# Pressure_sensor_-_SCP1000-D01.net
KiCad netlist of a schematic drawn in Altium Designer
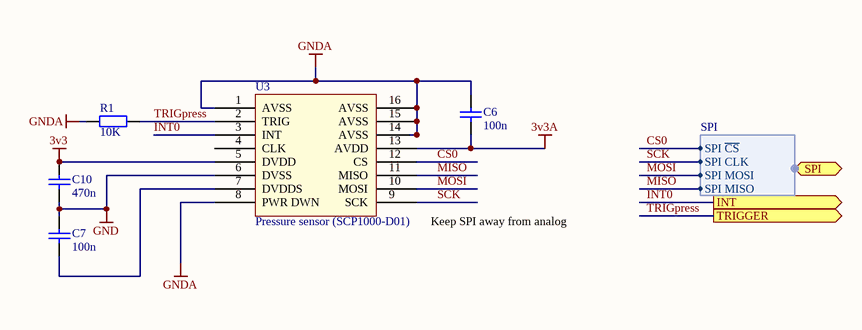
[diagram p0: Pressure sensor - SCP1000-D01.SchDoc]

(export (version "E")
  (design (tool "Eeschema 10.0.6"))
  (components
    (comp (ref "C6")
      (value "100n")
      (footprint "C0805")
      (fields (field (name "TOLERANCE") "0.1") (field (name "AUTHOR") "Willy Pietersz"))
      (libsource (lib "OurDb") (part "cap_NonPolar"))
    )
    (comp (ref "C7")
      (value "100n")
      (footprint "C0805")
      (fields (field (name "TOLERANCE") "0.1") (field (name "AUTHOR") "Willy Pietersz"))
      (libsource (lib "OurDb") (part "cap_NonPolar"))
    )
    (comp (ref "C10")
      (value "470n")
      (footprint "C0805")
      (fields (field (name "TOLERANCE") "0.1") (field (name "AUTHOR") "Willy Pietersz"))
      (libsource (lib "OurDb") (part "cap_NonPolar"))
    )
    (comp (ref "R1")
      (value "10K")
      (footprint "R0805")
      (description "Resistor")
      (fields
        (field (name "POWER") "0.25W")
        (field (name "TOLERANCE") "0.05")
        (field (name "PUBLISHER") "Altium Limited")
        (field (name "AUTHOR") "Willy Pietersz")
      )
      (libsource (lib "OurDb") (part "RESISTOR"))
    )
    (comp (ref "U3")
      (value "Pressure sensor (SCP1000-D01)")
      (footprint "SCP1000-D01")
      (fields (field (name "PART NUMBER") "SCP1000-D01"))
      (libsource (lib "OurDb") (part "SCP1000-D01"))
    )
  )
  (nets
    (net (code "2") (name "/CS0") (class "Default")
      (node (ref "U3") (pin "12") (pinfunction "CS_12") (pintype "passive"))
    )
    (net (code "3") (name "/INT0") (class "Default")
      (node (ref "U3") (pin "3") (pinfunction "INT_3") (pintype "passive"))
    )
    (net (code "4") (name "/MISO") (class "Default")
      (node (ref "U3") (pin "11") (pinfunction "MISO_11") (pintype "passive"))
    )
    (net (code "5") (name "/MOSI") (class "Default")
      (node (ref "U3") (pin "10") (pinfunction "MOSI_10") (pintype "passive"))
    )
    (net (code "6") (name "/SCK") (class "Default")
      (node (ref "U3") (pin "9") (pinfunction "SCK_9") (pintype "passive"))
    )
    (net (code "7") (name "/TRIGpress") (class "Default")
      (node (ref "R1") (pin "2") (pinfunction "2_2") (pintype "passive"))
      (node (ref "U3") (pin "2") (pinfunction "TRIG_2") (pintype "passive"))
    )
    (net (code "9") (name "3v3") (class "Default")
      (node (ref "C10") (pin "2") (pinfunction "2_2") (pintype "passive"))
      (node (ref "U3") (pin "5") (pinfunction "DVDD_5") (pintype "passive"))
    )
    (net (code "10") (name "3v3A") (class "Default")
      (node (ref "C6") (pin "1") (pinfunction "1_1") (pintype "passive"))
      (node (ref "U3") (pin "13") (pinfunction "AVDD_13") (pintype "passive"))
    )
    (net (code "11") (name "GND") (class "Default")
      (node (ref "C10") (pin "1") (pinfunction "1_1") (pintype "passive"))
      (node (ref "C7") (pin "2") (pinfunction "2_2") (pintype "passive"))
      (node (ref "U3") (pin "6") (pinfunction "DVSS_6") (pintype "passive"))
    )
    (net (code "12") (name "GNDA") (class "Default")
      (node (ref "C6") (pin "2") (pinfunction "2_2") (pintype "passive"))
      (node (ref "R1") (pin "1") (pinfunction "1_1") (pintype "passive"))
      (node (ref "U3") (pin "1") (pinfunction "AVSS_1") (pintype "passive"))
      (node (ref "U3") (pin "14") (pinfunction "AVSS_14") (pintype "passive"))
      (node (ref "U3") (pin "15") (pinfunction "AVSS_15") (pintype "passive"))
      (node (ref "U3") (pin "16") (pinfunction "AVSS_16") (pintype "passive"))
      (node (ref "U3") (pin "8") (pinfunction "PWR_DWN_8") (pintype "passive"))
    )
    (net (code "13") (name "Net-(U3-DVDDS)") (class "Default")
      (node (ref "C7") (pin "1") (pinfunction "1_1") (pintype "passive"))
      (node (ref "U3") (pin "7") (pinfunction "DVDDS_7") (pintype "passive"))
    )
    (net (code "14") (name "unconnected-(U3-CLK-Pad4)") (class "Default")
      (node (ref "U3") (pin "4") (pinfunction "CLK_4") (pintype "passive"))
    )
  )
)
